# LED_s_1Teclado.net
KiCad netlist of a schematic drawn in Altium Designer
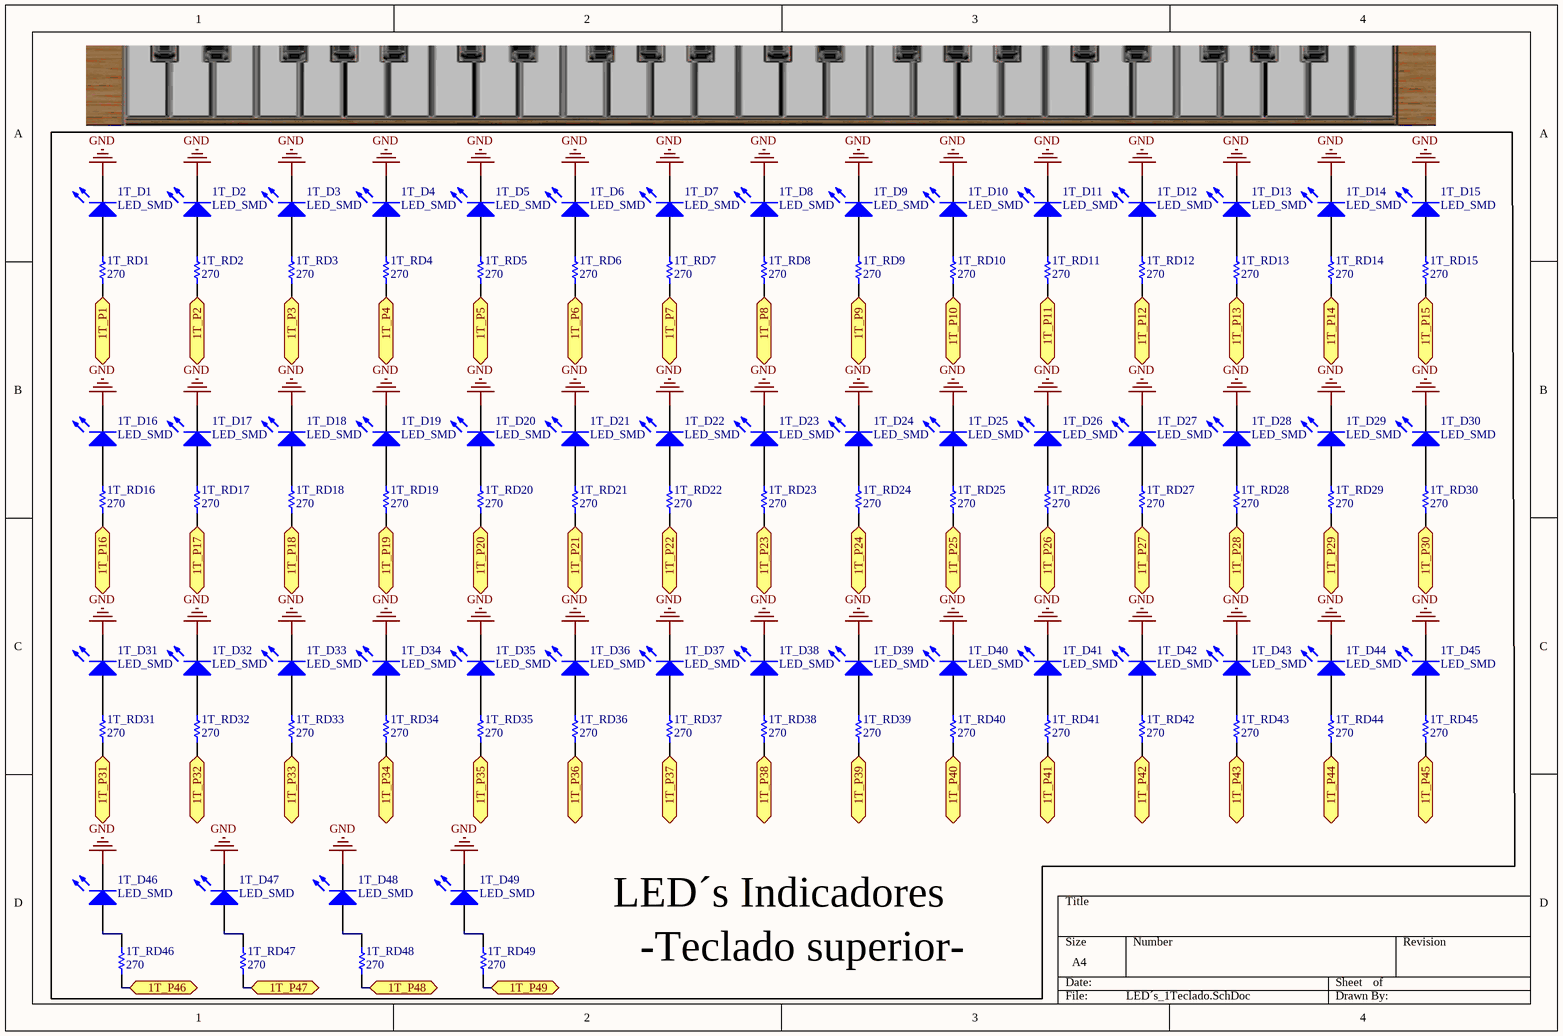
[diagram p0: LED´s_1Teclado.SchDoc]

(export (version "E")
  (design (tool "Eeschema 10.0.6"))
  (components
    (comp (ref "1T_D1")
      (value "LED_SMD")
      (footprint "0805")
      (description "LED SMD")
      (fields (field (name "PUBLISHER") "Altium Limited"))
      (libsource (lib "Libreria_Organo") (part "LED_SMD"))
    )
    (comp (ref "1T_D2")
      (value "LED_SMD")
      (footprint "0805")
      (description "LED SMD")
      (fields (field (name "PUBLISHER") "Altium Limited"))
      (libsource (lib "Libreria_Organo") (part "LED_SMD"))
    )
    (comp (ref "1T_D3")
      (value "LED_SMD")
      (footprint "0805")
      (description "LED SMD")
      (fields (field (name "PUBLISHER") "Altium Limited"))
      (libsource (lib "Libreria_Organo") (part "LED_SMD"))
    )
    (comp (ref "1T_D4")
      (value "LED_SMD")
      (footprint "0805")
      (description "LED SMD")
      (fields (field (name "PUBLISHER") "Altium Limited"))
      (libsource (lib "Libreria_Organo") (part "LED_SMD"))
    )
    (comp (ref "1T_D5")
      (value "LED_SMD")
      (footprint "0805")
      (description "LED SMD")
      (fields (field (name "PUBLISHER") "Altium Limited"))
      (libsource (lib "Libreria_Organo") (part "LED_SMD"))
    )
    (comp (ref "1T_D6")
      (value "LED_SMD")
      (footprint "0805")
      (description "LED SMD")
      (fields (field (name "PUBLISHER") "Altium Limited"))
      (libsource (lib "Libreria_Organo") (part "LED_SMD"))
    )
    (comp (ref "1T_D7")
      (value "LED_SMD")
      (footprint "0805")
      (description "LED SMD")
      (fields (field (name "PUBLISHER") "Altium Limited"))
      (libsource (lib "Libreria_Organo") (part "LED_SMD"))
    )
    (comp (ref "1T_D8")
      (value "LED_SMD")
      (footprint "0805")
      (description "LED SMD")
      (fields (field (name "PUBLISHER") "Altium Limited"))
      (libsource (lib "Libreria_Organo") (part "LED_SMD"))
    )
    (comp (ref "1T_D9")
      (value "LED_SMD")
      (footprint "0805")
      (description "LED SMD")
      (fields (field (name "PUBLISHER") "Altium Limited"))
      (libsource (lib "Libreria_Organo") (part "LED_SMD"))
    )
    (comp (ref "1T_D10")
      (value "LED_SMD")
      (footprint "0805")
      (description "LED SMD")
      (fields (field (name "PUBLISHER") "Altium Limited"))
      (libsource (lib "Libreria_Organo") (part "LED_SMD"))
    )
    (comp (ref "1T_D11")
      (value "LED_SMD")
      (footprint "0805")
      (description "LED SMD")
      (fields (field (name "PUBLISHER") "Altium Limited"))
      (libsource (lib "Libreria_Organo") (part "LED_SMD"))
    )
    (comp (ref "1T_D12")
      (value "LED_SMD")
      (footprint "0805")
      (description "LED SMD")
      (fields (field (name "PUBLISHER") "Altium Limited"))
      (libsource (lib "Libreria_Organo") (part "LED_SMD"))
    )
    (comp (ref "1T_D13")
      (value "LED_SMD")
      (footprint "0805")
      (description "LED SMD")
      (fields (field (name "PUBLISHER") "Altium Limited"))
      (libsource (lib "Libreria_Organo") (part "LED_SMD"))
    )
    (comp (ref "1T_D14")
      (value "LED_SMD")
      (footprint "0805")
      (description "LED SMD")
      (fields (field (name "PUBLISHER") "Altium Limited"))
      (libsource (lib "Libreria_Organo") (part "LED_SMD"))
    )
    (comp (ref "1T_D15")
      (value "LED_SMD")
      (footprint "0805")
      (description "LED SMD")
      (fields (field (name "PUBLISHER") "Altium Limited"))
      (libsource (lib "Libreria_Organo") (part "LED_SMD"))
    )
    (comp (ref "1T_D16")
      (value "LED_SMD")
      (footprint "0805")
      (description "LED SMD")
      (fields (field (name "PUBLISHER") "Altium Limited"))
      (libsource (lib "Libreria_Organo") (part "LED_SMD"))
    )
    (comp (ref "1T_D17")
      (value "LED_SMD")
      (footprint "0805")
      (description "LED SMD")
      (fields (field (name "PUBLISHER") "Altium Limited"))
      (libsource (lib "Libreria_Organo") (part "LED_SMD"))
    )
    (comp (ref "1T_D18")
      (value "LED_SMD")
      (footprint "0805")
      (description "LED SMD")
      (fields (field (name "PUBLISHER") "Altium Limited"))
      (libsource (lib "Libreria_Organo") (part "LED_SMD"))
    )
    (comp (ref "1T_D19")
      (value "LED_SMD")
      (footprint "0805")
      (description "LED SMD")
      (fields (field (name "PUBLISHER") "Altium Limited"))
      (libsource (lib "Libreria_Organo") (part "LED_SMD"))
    )
    (comp (ref "1T_D20")
      (value "LED_SMD")
      (footprint "0805")
      (description "LED SMD")
      (fields (field (name "PUBLISHER") "Altium Limited"))
      (libsource (lib "Libreria_Organo") (part "LED_SMD"))
    )
    (comp (ref "1T_D21")
      (value "LED_SMD")
      (footprint "0805")
      (description "LED SMD")
      (fields (field (name "PUBLISHER") "Altium Limited"))
      (libsource (lib "Libreria_Organo") (part "LED_SMD"))
    )
    (comp (ref "1T_D22")
      (value "LED_SMD")
      (footprint "0805")
      (description "LED SMD")
      (fields (field (name "PUBLISHER") "Altium Limited"))
      (libsource (lib "Libreria_Organo") (part "LED_SMD"))
    )
    (comp (ref "1T_D23")
      (value "LED_SMD")
      (footprint "0805")
      (description "LED SMD")
      (fields (field (name "PUBLISHER") "Altium Limited"))
      (libsource (lib "Libreria_Organo") (part "LED_SMD"))
    )
    (comp (ref "1T_D24")
      (value "LED_SMD")
      (footprint "0805")
      (description "LED SMD")
      (fields (field (name "PUBLISHER") "Altium Limited"))
      (libsource (lib "Libreria_Organo") (part "LED_SMD"))
    )
    (comp (ref "1T_D25")
      (value "LED_SMD")
      (footprint "0805")
      (description "LED SMD")
      (fields (field (name "PUBLISHER") "Altium Limited"))
      (libsource (lib "Libreria_Organo") (part "LED_SMD"))
    )
    (comp (ref "1T_D26")
      (value "LED_SMD")
      (footprint "0805")
      (description "LED SMD")
      (fields (field (name "PUBLISHER") "Altium Limited"))
      (libsource (lib "Libreria_Organo") (part "LED_SMD"))
    )
    (comp (ref "1T_D27")
      (value "LED_SMD")
      (footprint "0805")
      (description "LED SMD")
      (fields (field (name "PUBLISHER") "Altium Limited"))
      (libsource (lib "Libreria_Organo") (part "LED_SMD"))
    )
    (comp (ref "1T_D28")
      (value "LED_SMD")
      (footprint "0805")
      (description "LED SMD")
      (fields (field (name "PUBLISHER") "Altium Limited"))
      (libsource (lib "Libreria_Organo") (part "LED_SMD"))
    )
    (comp (ref "1T_D29")
      (value "LED_SMD")
      (footprint "0805")
      (description "LED SMD")
      (fields (field (name "PUBLISHER") "Altium Limited"))
      (libsource (lib "Libreria_Organo") (part "LED_SMD"))
    )
    (comp (ref "1T_D30")
      (value "LED_SMD")
      (footprint "0805")
      (description "LED SMD")
      (fields (field (name "PUBLISHER") "Altium Limited"))
      (libsource (lib "Libreria_Organo") (part "LED_SMD"))
    )
    (comp (ref "1T_D31")
      (value "LED_SMD")
      (footprint "0805")
      (description "LED SMD")
      (fields (field (name "PUBLISHER") "Altium Limited"))
      (libsource (lib "Libreria_Organo") (part "LED_SMD"))
    )
    (comp (ref "1T_D32")
      (value "LED_SMD")
      (footprint "0805")
      (description "LED SMD")
      (fields (field (name "PUBLISHER") "Altium Limited"))
      (libsource (lib "Libreria_Organo") (part "LED_SMD"))
    )
    (comp (ref "1T_D33")
      (value "LED_SMD")
      (footprint "0805")
      (description "LED SMD")
      (fields (field (name "PUBLISHER") "Altium Limited"))
      (libsource (lib "Libreria_Organo") (part "LED_SMD"))
    )
    (comp (ref "1T_D34")
      (value "LED_SMD")
      (footprint "0805")
      (description "LED SMD")
      (fields (field (name "PUBLISHER") "Altium Limited"))
      (libsource (lib "Libreria_Organo") (part "LED_SMD"))
    )
    (comp (ref "1T_D35")
      (value "LED_SMD")
      (footprint "0805")
      (description "LED SMD")
      (fields (field (name "PUBLISHER") "Altium Limited"))
      (libsource (lib "Libreria_Organo") (part "LED_SMD"))
    )
    (comp (ref "1T_D36")
      (value "LED_SMD")
      (footprint "0805")
      (description "LED SMD")
      (fields (field (name "PUBLISHER") "Altium Limited"))
      (libsource (lib "Libreria_Organo") (part "LED_SMD"))
    )
    (comp (ref "1T_D37")
      (value "LED_SMD")
      (footprint "0805")
      (description "LED SMD")
      (fields (field (name "PUBLISHER") "Altium Limited"))
      (libsource (lib "Libreria_Organo") (part "LED_SMD"))
    )
    (comp (ref "1T_D38")
      (value "LED_SMD")
      (footprint "0805")
      (description "LED SMD")
      (fields (field (name "PUBLISHER") "Altium Limited"))
      (libsource (lib "Libreria_Organo") (part "LED_SMD"))
    )
    (comp (ref "1T_D39")
      (value "LED_SMD")
      (footprint "0805")
      (description "LED SMD")
      (fields (field (name "PUBLISHER") "Altium Limited"))
      (libsource (lib "Libreria_Organo") (part "LED_SMD"))
    )
    (comp (ref "1T_D40")
      (value "LED_SMD")
      (footprint "0805")
      (description "LED SMD")
      (fields (field (name "PUBLISHER") "Altium Limited"))
      (libsource (lib "Libreria_Organo") (part "LED_SMD"))
    )
    (comp (ref "1T_D41")
      (value "LED_SMD")
      (footprint "0805")
      (description "LED SMD")
      (fields (field (name "PUBLISHER") "Altium Limited"))
      (libsource (lib "Libreria_Organo") (part "LED_SMD"))
    )
    (comp (ref "1T_D42")
      (value "LED_SMD")
      (footprint "0805")
      (description "LED SMD")
      (fields (field (name "PUBLISHER") "Altium Limited"))
      (libsource (lib "Libreria_Organo") (part "LED_SMD"))
    )
    (comp (ref "1T_D43")
      (value "LED_SMD")
      (footprint "0805")
      (description "LED SMD")
      (fields (field (name "PUBLISHER") "Altium Limited"))
      (libsource (lib "Libreria_Organo") (part "LED_SMD"))
    )
    (comp (ref "1T_D44")
      (value "LED_SMD")
      (footprint "0805")
      (description "LED SMD")
      (fields (field (name "PUBLISHER") "Altium Limited"))
      (libsource (lib "Libreria_Organo") (part "LED_SMD"))
    )
    (comp (ref "1T_D45")
      (value "LED_SMD")
      (footprint "0805")
      (description "LED SMD")
      (fields (field (name "PUBLISHER") "Altium Limited"))
      (libsource (lib "Libreria_Organo") (part "LED_SMD"))
    )
    (comp (ref "1T_D46")
      (value "LED_SMD")
      (footprint "0805")
      (description "LED SMD")
      (fields (field (name "PUBLISHER") "Altium Limited"))
      (libsource (lib "Libreria_Organo") (part "LED_SMD"))
    )
    (comp (ref "1T_D47")
      (value "LED_SMD")
      (footprint "0805")
      (description "LED SMD")
      (fields (field (name "PUBLISHER") "Altium Limited"))
      (libsource (lib "Libreria_Organo") (part "LED_SMD"))
    )
    (comp (ref "1T_D48")
      (value "LED_SMD")
      (footprint "0805")
      (description "LED SMD")
      (fields (field (name "PUBLISHER") "Altium Limited"))
      (libsource (lib "Libreria_Organo") (part "LED_SMD"))
    )
    (comp (ref "1T_D49")
      (value "LED_SMD")
      (footprint "0805")
      (description "LED SMD")
      (fields (field (name "PUBLISHER") "Altium Limited"))
      (libsource (lib "Libreria_Organo") (part "LED_SMD"))
    )
    (comp (ref "1T_RD1")
      (value "270")
      (footprint "0805 Chip Res")
      (description "Res Chip 0805")
      (fields (field (name "PUBLISHER") "Altium Limited"))
      (libsource (lib "Libreria_Organo") (part "Resistencia"))
    )
    (comp (ref "1T_RD2")
      (value "270")
      (footprint "0805 Chip Res")
      (description "Res Chip 0805")
      (fields (field (name "PUBLISHER") "Altium Limited"))
      (libsource (lib "Libreria_Organo") (part "Resistencia"))
    )
    (comp (ref "1T_RD3")
      (value "270")
      (footprint "0805 Chip Res")
      (description "Res Chip 0805")
      (fields (field (name "PUBLISHER") "Altium Limited"))
      (libsource (lib "Libreria_Organo") (part "Resistencia"))
    )
    (comp (ref "1T_RD4")
      (value "270")
      (footprint "0805 Chip Res")
      (description "Res Chip 0805")
      (fields (field (name "PUBLISHER") "Altium Limited"))
      (libsource (lib "Libreria_Organo") (part "Resistencia"))
    )
    (comp (ref "1T_RD5")
      (value "270")
      (footprint "0805 Chip Res")
      (description "Res Chip 0805")
      (fields (field (name "PUBLISHER") "Altium Limited"))
      (libsource (lib "Libreria_Organo") (part "Resistencia"))
    )
    (comp (ref "1T_RD6")
      (value "270")
      (footprint "0805 Chip Res")
      (description "Res Chip 0805")
      (fields (field (name "PUBLISHER") "Altium Limited"))
      (libsource (lib "Libreria_Organo") (part "Resistencia"))
    )
    (comp (ref "1T_RD7")
      (value "270")
      (footprint "0805 Chip Res")
      (description "Res Chip 0805")
      (fields (field (name "PUBLISHER") "Altium Limited"))
      (libsource (lib "Libreria_Organo") (part "Resistencia"))
    )
    (comp (ref "1T_RD8")
      (value "270")
      (footprint "0805 Chip Res")
      (description "Res Chip 0805")
      (fields (field (name "PUBLISHER") "Altium Limited"))
      (libsource (lib "Libreria_Organo") (part "Resistencia"))
    )
    (comp (ref "1T_RD9")
      (value "270")
      (footprint "0805 Chip Res")
      (description "Res Chip 0805")
      (fields (field (name "PUBLISHER") "Altium Limited"))
      (libsource (lib "Libreria_Organo") (part "Resistencia"))
    )
    (comp (ref "1T_RD10")
      (value "270")
      (footprint "0805 Chip Res")
      (description "Res Chip 0805")
      (fields (field (name "PUBLISHER") "Altium Limited"))
      (libsource (lib "Libreria_Organo") (part "Resistencia"))
    )
    (comp (ref "1T_RD11")
      (value "270")
      (footprint "0805 Chip Res")
      (description "Res Chip 0805")
      (fields (field (name "PUBLISHER") "Altium Limited"))
      (libsource (lib "Libreria_Organo") (part "Resistencia"))
    )
    (comp (ref "1T_RD12")
      (value "270")
      (footprint "0805 Chip Res")
      (description "Res Chip 0805")
      (fields (field (name "PUBLISHER") "Altium Limited"))
      (libsource (lib "Libreria_Organo") (part "Resistencia"))
    )
    (comp (ref "1T_RD13")
      (value "270")
      (footprint "0805 Chip Res")
      (description "Res Chip 0805")
      (fields (field (name "PUBLISHER") "Altium Limited"))
      (libsource (lib "Libreria_Organo") (part "Resistencia"))
    )
    (comp (ref "1T_RD14")
      (value "270")
      (footprint "0805 Chip Res")
      (description "Res Chip 0805")
      (fields (field (name "PUBLISHER") "Altium Limited"))
      (libsource (lib "Libreria_Organo") (part "Resistencia"))
    )
    (comp (ref "1T_RD15")
      (value "270")
      (footprint "0805 Chip Res")
      (description "Res Chip 0805")
      (fields (field (name "PUBLISHER") "Altium Limited"))
      (libsource (lib "Libreria_Organo") (part "Resistencia"))
    )
    (comp (ref "1T_RD16")
      (value "270")
      (footprint "0805 Chip Res")
      (description "Res Chip 0805")
      (fields (field (name "PUBLISHER") "Altium Limited"))
      (libsource (lib "Libreria_Organo") (part "Resistencia"))
    )
    (comp (ref "1T_RD17")
      (value "270")
      (footprint "0805 Chip Res")
      (description "Res Chip 0805")
      (fields (field (name "PUBLISHER") "Altium Limited"))
      (libsource (lib "Libreria_Organo") (part "Resistencia"))
    )
    (comp (ref "1T_RD18")
      (value "270")
      (footprint "0805 Chip Res")
      (description "Res Chip 0805")
      (fields (field (name "PUBLISHER") "Altium Limited"))
      (libsource (lib "Libreria_Organo") (part "Resistencia"))
    )
    (comp (ref "1T_RD19")
      (value "270")
      (footprint "0805 Chip Res")
      (description "Res Chip 0805")
      (fields (field (name "PUBLISHER") "Altium Limited"))
      (libsource (lib "Libreria_Organo") (part "Resistencia"))
    )
    (comp (ref "1T_RD20")
      (value "270")
      (footprint "0805 Chip Res")
      (description "Res Chip 0805")
      (fields (field (name "PUBLISHER") "Altium Limited"))
      (libsource (lib "Libreria_Organo") (part "Resistencia"))
    )
    (comp (ref "1T_RD21")
      (value "270")
      (footprint "0805 Chip Res")
      (description "Res Chip 0805")
      (fields (field (name "PUBLISHER") "Altium Limited"))
      (libsource (lib "Libreria_Organo") (part "Resistencia"))
    )
    (comp (ref "1T_RD22")
      (value "270")
      (footprint "0805 Chip Res")
      (description "Res Chip 0805")
      (fields (field (name "PUBLISHER") "Altium Limited"))
      (libsource (lib "Libreria_Organo") (part "Resistencia"))
    )
    (comp (ref "1T_RD23")
      (value "270")
      (footprint "0805 Chip Res")
      (description "Res Chip 0805")
      (fields (field (name "PUBLISHER") "Altium Limited"))
      (libsource (lib "Libreria_Organo") (part "Resistencia"))
    )
    (comp (ref "1T_RD24")
      (value "270")
      (footprint "0805 Chip Res")
      (description "Res Chip 0805")
      (fields (field (name "PUBLISHER") "Altium Limited"))
      (libsource (lib "Libreria_Organo") (part "Resistencia"))
    )
    (comp (ref "1T_RD25")
      (value "270")
      (footprint "0805 Chip Res")
      (description "Res Chip 0805")
      (fields (field (name "PUBLISHER") "Altium Limited"))
      (libsource (lib "Libreria_Organo") (part "Resistencia"))
    )
    (comp (ref "1T_RD26")
      (value "270")
      (footprint "0805 Chip Res")
      (description "Res Chip 0805")
      (fields (field (name "PUBLISHER") "Altium Limited"))
      (libsource (lib "Libreria_Organo") (part "Resistencia"))
    )
    (comp (ref "1T_RD27")
      (value "270")
      (footprint "0805 Chip Res")
      (description "Res Chip 0805")
      (fields (field (name "PUBLISHER") "Altium Limited"))
      (libsource (lib "Libreria_Organo") (part "Resistencia"))
    )
    (comp (ref "1T_RD28")
      (value "270")
      (footprint "0805 Chip Res")
      (description "Res Chip 0805")
      (fields (field (name "PUBLISHER") "Altium Limited"))
      (libsource (lib "Libreria_Organo") (part "Resistencia"))
    )
    (comp (ref "1T_RD29")
      (value "270")
      (footprint "0805 Chip Res")
      (description "Res Chip 0805")
      (fields (field (name "PUBLISHER") "Altium Limited"))
      (libsource (lib "Libreria_Organo") (part "Resistencia"))
    )
    (comp (ref "1T_RD30")
      (value "270")
      (footprint "0805 Chip Res")
      (description "Res Chip 0805")
      (fields (field (name "PUBLISHER") "Altium Limited"))
      (libsource (lib "Libreria_Organo") (part "Resistencia"))
    )
    (comp (ref "1T_RD31")
      (value "270")
      (footprint "0805 Chip Res")
      (description "Res Chip 0805")
      (fields (field (name "PUBLISHER") "Altium Limited"))
      (libsource (lib "Libreria_Organo") (part "Resistencia"))
    )
    (comp (ref "1T_RD32")
      (value "270")
      (footprint "0805 Chip Res")
      (description "Res Chip 0805")
      (fields (field (name "PUBLISHER") "Altium Limited"))
      (libsource (lib "Libreria_Organo") (part "Resistencia"))
    )
    (comp (ref "1T_RD33")
      (value "270")
      (footprint "0805 Chip Res")
      (description "Res Chip 0805")
      (fields (field (name "PUBLISHER") "Altium Limited"))
      (libsource (lib "Libreria_Organo") (part "Resistencia"))
    )
    (comp (ref "1T_RD34")
      (value "270")
      (footprint "0805 Chip Res")
      (description "Res Chip 0805")
      (fields (field (name "PUBLISHER") "Altium Limited"))
      (libsource (lib "Libreria_Organo") (part "Resistencia"))
    )
    (comp (ref "1T_RD35")
      (value "270")
      (footprint "0805 Chip Res")
      (description "Res Chip 0805")
      (fields (field (name "PUBLISHER") "Altium Limited"))
      (libsource (lib "Libreria_Organo") (part "Resistencia"))
    )
    (comp (ref "1T_RD36")
      (value "270")
      (footprint "0805 Chip Res")
      (description "Res Chip 0805")
      (fields (field (name "PUBLISHER") "Altium Limited"))
      (libsource (lib "Libreria_Organo") (part "Resistencia"))
    )
    (comp (ref "1T_RD37")
      (value "270")
      (footprint "0805 Chip Res")
      (description "Res Chip 0805")
      (fields (field (name "PUBLISHER") "Altium Limited"))
      (libsource (lib "Libreria_Organo") (part "Resistencia"))
    )
    (comp (ref "1T_RD38")
      (value "270")
      (footprint "0805 Chip Res")
      (description "Res Chip 0805")
      (fields (field (name "PUBLISHER") "Altium Limited"))
      (libsource (lib "Libreria_Organo") (part "Resistencia"))
    )
    (comp (ref "1T_RD39")
      (value "270")
      (footprint "0805 Chip Res")
      (description "Res Chip 0805")
      (fields (field (name "PUBLISHER") "Altium Limited"))
      (libsource (lib "Libreria_Organo") (part "Resistencia"))
    )
    (comp (ref "1T_RD40")
      (value "270")
      (footprint "0805 Chip Res")
      (description "Res Chip 0805")
      (fields (field (name "PUBLISHER") "Altium Limited"))
      (libsource (lib "Libreria_Organo") (part "Resistencia"))
    )
    (comp (ref "1T_RD41")
      (value "270")
      (footprint "0805 Chip Res")
      (description "Res Chip 0805")
      (fields (field (name "PUBLISHER") "Altium Limited"))
      (libsource (lib "Libreria_Organo") (part "Resistencia"))
    )
    (comp (ref "1T_RD42")
      (value "270")
      (footprint "0805 Chip Res")
      (description "Res Chip 0805")
      (fields (field (name "PUBLISHER") "Altium Limited"))
      (libsource (lib "Libreria_Organo") (part "Resistencia"))
    )
    (comp (ref "1T_RD43")
      (value "270")
      (footprint "0805 Chip Res")
      (description "Res Chip 0805")
      (fields (field (name "PUBLISHER") "Altium Limited"))
      (libsource (lib "Libreria_Organo") (part "Resistencia"))
    )
    (comp (ref "1T_RD44")
      (value "270")
      (footprint "0805 Chip Res")
      (description "Res Chip 0805")
      (fields (field (name "PUBLISHER") "Altium Limited"))
      (libsource (lib "Libreria_Organo") (part "Resistencia"))
    )
    (comp (ref "1T_RD45")
      (value "270")
      (footprint "0805 Chip Res")
      (description "Res Chip 0805")
      (fields (field (name "PUBLISHER") "Altium Limited"))
      (libsource (lib "Libreria_Organo") (part "Resistencia"))
    )
    (comp (ref "1T_RD46")
      (value "270")
      (footprint "0805 Chip Res")
      (description "Res Chip 0805")
      (fields (field (name "PUBLISHER") "Altium Limited"))
      (libsource (lib "Libreria_Organo") (part "Resistencia"))
    )
    (comp (ref "1T_RD47")
      (value "270")
      (footprint "0805 Chip Res")
      (description "Res Chip 0805")
      (fields (field (name "PUBLISHER") "Altium Limited"))
      (libsource (lib "Libreria_Organo") (part "Resistencia"))
    )
    (comp (ref "1T_RD48")
      (value "270")
      (footprint "0805 Chip Res")
      (description "Res Chip 0805")
      (fields (field (name "PUBLISHER") "Altium Limited"))
      (libsource (lib "Libreria_Organo") (part "Resistencia"))
    )
    (comp (ref "1T_RD49")
      (value "270")
      (footprint "0805 Chip Res")
      (description "Res Chip 0805")
      (fields (field (name "PUBLISHER") "Altium Limited"))
      (libsource (lib "Libreria_Organo") (part "Resistencia"))
    )
  )
  (nets
    (net (code "1") (name "/1T_P1") (class "Default")
      (node (ref "1T_RD1") (pin "1") (pinfunction "1_1") (pintype "passive"))
    )
    (net (code "2") (name "/1T_P2") (class "Default")
      (node (ref "1T_RD2") (pin "1") (pinfunction "1_1") (pintype "passive"))
    )
    (net (code "3") (name "/1T_P3") (class "Default")
      (node (ref "1T_RD3") (pin "1") (pinfunction "1_1") (pintype "passive"))
    )
    (net (code "4") (name "/1T_P4") (class "Default")
      (node (ref "1T_RD4") (pin "1") (pinfunction "1_1") (pintype "passive"))
    )
    (net (code "5") (name "/1T_P5") (class "Default")
      (node (ref "1T_RD5") (pin "1") (pinfunction "1_1") (pintype "passive"))
    )
    (net (code "6") (name "/1T_P6") (class "Default")
      (node (ref "1T_RD6") (pin "1") (pinfunction "1_1") (pintype "passive"))
    )
    (net (code "7") (name "/1T_P7") (class "Default")
      (node (ref "1T_RD7") (pin "1") (pinfunction "1_1") (pintype "passive"))
    )
    (net (code "8") (name "/1T_P8") (class "Default")
      (node (ref "1T_RD8") (pin "1") (pinfunction "1_1") (pintype "passive"))
    )
    (net (code "9") (name "/1T_P9") (class "Default")
      (node (ref "1T_RD9") (pin "1") (pinfunction "1_1") (pintype "passive"))
    )
    (net (code "10") (name "/1T_P10") (class "Default")
      (node (ref "1T_RD10") (pin "1") (pinfunction "1_1") (pintype "passive"))
    )
    (net (code "11") (name "/1T_P11") (class "Default")
      (node (ref "1T_RD11") (pin "1") (pinfunction "1_1") (pintype "passive"))
    )
    (net (code "12") (name "/1T_P12") (class "Default")
      (node (ref "1T_RD12") (pin "1") (pinfunction "1_1") (pintype "passive"))
    )
    (net (code "13") (name "/1T_P13") (class "Default")
      (node (ref "1T_RD13") (pin "1") (pinfunction "1_1") (pintype "passive"))
    )
    (net (code "14") (name "/1T_P14") (class "Default")
      (node (ref "1T_RD14") (pin "1") (pinfunction "1_1") (pintype "passive"))
    )
    (net (code "15") (name "/1T_P15") (class "Default")
      (node (ref "1T_RD15") (pin "1") (pinfunction "1_1") (pintype "passive"))
    )
    (net (code "16") (name "/1T_P16") (class "Default")
      (node (ref "1T_RD16") (pin "1") (pinfunction "1_1") (pintype "passive"))
    )
    (net (code "17") (name "/1T_P17") (class "Default")
      (node (ref "1T_RD17") (pin "1") (pinfunction "1_1") (pintype "passive"))
    )
    (net (code "18") (name "/1T_P18") (class "Default")
      (node (ref "1T_RD18") (pin "1") (pinfunction "1_1") (pintype "passive"))
    )
    (net (code "19") (name "/1T_P19") (class "Default")
      (node (ref "1T_RD19") (pin "1") (pinfunction "1_1") (pintype "passive"))
    )
    (net (code "20") (name "/1T_P20") (class "Default")
      (node (ref "1T_RD20") (pin "1") (pinfunction "1_1") (pintype "passive"))
    )
    (net (code "21") (name "/1T_P21") (class "Default")
      (node (ref "1T_RD21") (pin "1") (pinfunction "1_1") (pintype "passive"))
    )
    (net (code "22") (name "/1T_P22") (class "Default")
      (node (ref "1T_RD22") (pin "1") (pinfunction "1_1") (pintype "passive"))
    )
    (net (code "23") (name "/1T_P23") (class "Default")
      (node (ref "1T_RD23") (pin "1") (pinfunction "1_1") (pintype "passive"))
    )
    (net (code "24") (name "/1T_P24") (class "Default")
      (node (ref "1T_RD24") (pin "1") (pinfunction "1_1") (pintype "passive"))
    )
    (net (code "25") (name "/1T_P25") (class "Default")
      (node (ref "1T_RD25") (pin "1") (pinfunction "1_1") (pintype "passive"))
    )
    (net (code "26") (name "/1T_P26") (class "Default")
      (node (ref "1T_RD26") (pin "1") (pinfunction "1_1") (pintype "passive"))
    )
    (net (code "27") (name "/1T_P27") (class "Default")
      (node (ref "1T_RD27") (pin "1") (pinfunction "1_1") (pintype "passive"))
    )
    (net (code "28") (name "/1T_P28") (class "Default")
      (node (ref "1T_RD28") (pin "1") (pinfunction "1_1") (pintype "passive"))
    )
    (net (code "29") (name "/1T_P29") (class "Default")
      (node (ref "1T_RD29") (pin "1") (pinfunction "1_1") (pintype "passive"))
    )
    (net (code "30") (name "/1T_P30") (class "Default")
      (node (ref "1T_RD30") (pin "1") (pinfunction "1_1") (pintype "passive"))
    )
    (net (code "31") (name "/1T_P31") (class "Default")
      (node (ref "1T_RD31") (pin "1") (pinfunction "1_1") (pintype "passive"))
    )
    (net (code "32") (name "/1T_P32") (class "Default")
      (node (ref "1T_RD32") (pin "1") (pinfunction "1_1") (pintype "passive"))
    )
    (net (code "33") (name "/1T_P33") (class "Default")
      (node (ref "1T_RD33") (pin "1") (pinfunction "1_1") (pintype "passive"))
    )
    (net (code "34") (name "/1T_P34") (class "Default")
      (node (ref "1T_RD34") (pin "1") (pinfunction "1_1") (pintype "passive"))
    )
    (net (code "35") (name "/1T_P35") (class "Default")
      (node (ref "1T_RD35") (pin "1") (pinfunction "1_1") (pintype "passive"))
    )
    (net (code "36") (name "/1T_P36") (class "Default")
      (node (ref "1T_RD36") (pin "1") (pinfunction "1_1") (pintype "passive"))
    )
    (net (code "37") (name "/1T_P37") (class "Default")
      (node (ref "1T_RD37") (pin "1") (pinfunction "1_1") (pintype "passive"))
    )
    (net (code "38") (name "/1T_P38") (class "Default")
      (node (ref "1T_RD38") (pin "1") (pinfunction "1_1") (pintype "passive"))
    )
    (net (code "39") (name "/1T_P39") (class "Default")
      (node (ref "1T_RD39") (pin "1") (pinfunction "1_1") (pintype "passive"))
    )
    (net (code "40") (name "/1T_P40") (class "Default")
      (node (ref "1T_RD40") (pin "1") (pinfunction "1_1") (pintype "passive"))
    )
    (net (code "41") (name "/1T_P41") (class "Default")
      (node (ref "1T_RD41") (pin "1") (pinfunction "1_1") (pintype "passive"))
    )
    (net (code "42") (name "/1T_P42") (class "Default")
      (node (ref "1T_RD42") (pin "1") (pinfunction "1_1") (pintype "passive"))
    )
    (net (code "43") (name "/1T_P43") (class "Default")
      (node (ref "1T_RD43") (pin "1") (pinfunction "1_1") (pintype "passive"))
    )
    (net (code "44") (name "/1T_P44") (class "Default")
      (node (ref "1T_RD44") (pin "1") (pinfunction "1_1") (pintype "passive"))
    )
    (net (code "45") (name "/1T_P45") (class "Default")
      (node (ref "1T_RD45") (pin "1") (pinfunction "1_1") (pintype "passive"))
    )
    (net (code "46") (name "/1T_P46") (class "Default")
      (node (ref "1T_RD46") (pin "1") (pinfunction "1_1") (pintype "passive"))
    )
    (net (code "47") (name "/1T_P47") (class "Default")
      (node (ref "1T_RD47") (pin "1") (pinfunction "1_1") (pintype "passive"))
    )
    (net (code "48") (name "/1T_P48") (class "Default")
      (node (ref "1T_RD48") (pin "1") (pinfunction "1_1") (pintype "passive"))
    )
    (net (code "49") (name "/1T_P49") (class "Default")
      (node (ref "1T_RD49") (pin "1") (pinfunction "1_1") (pintype "passive"))
    )
    (net (code "50") (name "GND") (class "Default")
      (node (ref "1T_D1") (pin "2") (pinfunction "K_2") (pintype "passive"))
      (node (ref "1T_D10") (pin "2") (pinfunction "K_2") (pintype "passive"))
      (node (ref "1T_D11") (pin "2") (pinfunction "K_2") (pintype "passive"))
      (node (ref "1T_D12") (pin "2") (pinfunction "K_2") (pintype "passive"))
      (node (ref "1T_D13") (pin "2") (pinfunction "K_2") (pintype "passive"))
      (node (ref "1T_D14") (pin "2") (pinfunction "K_2") (pintype "passive"))
      (node (ref "1T_D15") (pin "2") (pinfunction "K_2") (pintype "passive"))
      (node (ref "1T_D16") (pin "2") (pinfunction "K_2") (pintype "passive"))
      (node (ref "1T_D17") (pin "2") (pinfunction "K_2") (pintype "passive"))
      (node (ref "1T_D18") (pin "2") (pinfunction "K_2") (pintype "passive"))
      (node (ref "1T_D19") (pin "2") (pinfunction "K_2") (pintype "passive"))
      (node (ref "1T_D2") (pin "2") (pinfunction "K_2") (pintype "passive"))
      (node (ref "1T_D20") (pin "2") (pinfunction "K_2") (pintype "passive"))
      (node (ref "1T_D21") (pin "2") (pinfunction "K_2") (pintype "passive"))
      (node (ref "1T_D22") (pin "2") (pinfunction "K_2") (pintype "passive"))
      (node (ref "1T_D23") (pin "2") (pinfunction "K_2") (pintype "passive"))
      (node (ref "1T_D24") (pin "2") (pinfunction "K_2") (pintype "passive"))
      (node (ref "1T_D25") (pin "2") (pinfunction "K_2") (pintype "passive"))
      (node (ref "1T_D26") (pin "2") (pinfunction "K_2") (pintype "passive"))
      (node (ref "1T_D27") (pin "2") (pinfunction "K_2") (pintype "passive"))
      (node (ref "1T_D28") (pin "2") (pinfunction "K_2") (pintype "passive"))
      (node (ref "1T_D29") (pin "2") (pinfunction "K_2") (pintype "passive"))
      (node (ref "1T_D3") (pin "2") (pinfunction "K_2") (pintype "passive"))
      (node (ref "1T_D30") (pin "2") (pinfunction "K_2") (pintype "passive"))
      (node (ref "1T_D31") (pin "2") (pinfunction "K_2") (pintype "passive"))
      (node (ref "1T_D32") (pin "2") (pinfunction "K_2") (pintype "passive"))
      (node (ref "1T_D33") (pin "2") (pinfunction "K_2") (pintype "passive"))
      (node (ref "1T_D34") (pin "2") (pinfunction "K_2") (pintype "passive"))
      (node (ref "1T_D35") (pin "2") (pinfunction "K_2") (pintype "passive"))
      (node (ref "1T_D36") (pin "2") (pinfunction "K_2") (pintype "passive"))
      (node (ref "1T_D37") (pin "2") (pinfunction "K_2") (pintype "passive"))
      (node (ref "1T_D38") (pin "2") (pinfunction "K_2") (pintype "passive"))
      (node (ref "1T_D39") (pin "2") (pinfunction "K_2") (pintype "passive"))
      (node (ref "1T_D4") (pin "2") (pinfunction "K_2") (pintype "passive"))
      (node (ref "1T_D40") (pin "2") (pinfunction "K_2") (pintype "passive"))
      (node (ref "1T_D41") (pin "2") (pinfunction "K_2") (pintype "passive"))
      (node (ref "1T_D42") (pin "2") (pinfunction "K_2") (pintype "passive"))
      (node (ref "1T_D43") (pin "2") (pinfunction "K_2") (pintype "passive"))
      (node (ref "1T_D44") (pin "2") (pinfunction "K_2") (pintype "passive"))
      (node (ref "1T_D45") (pin "2") (pinfunction "K_2") (pintype "passive"))
      (node (ref "1T_D46") (pin "2") (pinfunction "K_2") (pintype "passive"))
      (node (ref "1T_D47") (pin "2") (pinfunction "K_2") (pintype "passive"))
      (node (ref "1T_D48") (pin "2") (pinfunction "K_2") (pintype "passive"))
      (node (ref "1T_D49") (pin "2") (pinfunction "K_2") (pintype "passive"))
      (node (ref "1T_D5") (pin "2") (pinfunction "K_2") (pintype "passive"))
      (node (ref "1T_D6") (pin "2") (pinfunction "K_2") (pintype "passive"))
      (node (ref "1T_D7") (pin "2") (pinfunction "K_2") (pintype "passive"))
      (node (ref "1T_D8") (pin "2") (pinfunction "K_2") (pintype "passive"))
      (node (ref "1T_D9") (pin "2") (pinfunction "K_2") (pintype "passive"))
    )
    (net (code "51") (name "Net-(1T_D1-A)") (class "Default")
      (node (ref "1T_D1") (pin "1") (pinfunction "A_1") (pintype "passive"))
      (node (ref "1T_RD1") (pin "2") (pinfunction "2_2") (pintype "passive"))
    )
    (net (code "52") (name "Net-(1T_D2-A)") (class "Default")
      (node (ref "1T_D2") (pin "1") (pinfunction "A_1") (pintype "passive"))
      (node (ref "1T_RD2") (pin "2") (pinfunction "2_2") (pintype "passive"))
    )
    (net (code "53") (name "Net-(1T_D3-A)") (class "Default")
      (node (ref "1T_D3") (pin "1") (pinfunction "A_1") (pintype "passive"))
      (node (ref "1T_RD3") (pin "2") (pinfunction "2_2") (pintype "passive"))
    )
    (net (code "54") (name "Net-(1T_D4-A)") (class "Default")
      (node (ref "1T_D4") (pin "1") (pinfunction "A_1") (pintype "passive"))
      (node (ref "1T_RD4") (pin "2") (pinfunction "2_2") (pintype "passive"))
    )
    (net (code "55") (name "Net-(1T_D5-A)") (class "Default")
      (node (ref "1T_D5") (pin "1") (pinfunction "A_1") (pintype "passive"))
      (node (ref "1T_RD5") (pin "2") (pinfunction "2_2") (pintype "passive"))
    )
    (net (code "56") (name "Net-(1T_D6-A)") (class "Default")
      (node (ref "1T_D6") (pin "1") (pinfunction "A_1") (pintype "passive"))
      (node (ref "1T_RD6") (pin "2") (pinfunction "2_2") (pintype "passive"))
    )
    (net (code "57") (name "Net-(1T_D7-A)") (class "Default")
      (node (ref "1T_D7") (pin "1") (pinfunction "A_1") (pintype "passive"))
      (node (ref "1T_RD7") (pin "2") (pinfunction "2_2") (pintype "passive"))
    )
    (net (code "58") (name "Net-(1T_D8-A)") (class "Default")
      (node (ref "1T_D8") (pin "1") (pinfunction "A_1") (pintype "passive"))
      (node (ref "1T_RD8") (pin "2") (pinfunction "2_2") (pintype "passive"))
    )
    (net (code "59") (name "Net-(1T_D9-A)") (class "Default")
      (node (ref "1T_D9") (pin "1") (pinfunction "A_1") (pintype "passive"))
      (node (ref "1T_RD9") (pin "2") (pinfunction "2_2") (pintype "passive"))
    )
    (net (code "60") (name "Net-(1T_D10-A)") (class "Default")
      (node (ref "1T_D10") (pin "1") (pinfunction "A_1") (pintype "passive"))
      (node (ref "1T_RD10") (pin "2") (pinfunction "2_2") (pintype "passive"))
    )
    (net (code "61") (name "Net-(1T_D11-A)") (class "Default")
      (node (ref "1T_D11") (pin "1") (pinfunction "A_1") (pintype "passive"))
      (node (ref "1T_RD11") (pin "2") (pinfunction "2_2") (pintype "passive"))
    )
    (net (code "62") (name "Net-(1T_D12-A)") (class "Default")
      (node (ref "1T_D12") (pin "1") (pinfunction "A_1") (pintype "passive"))
      (node (ref "1T_RD12") (pin "2") (pinfunction "2_2") (pintype "passive"))
    )
    (net (code "63") (name "Net-(1T_D13-A)") (class "Default")
      (node (ref "1T_D13") (pin "1") (pinfunction "A_1") (pintype "passive"))
      (node (ref "1T_RD13") (pin "2") (pinfunction "2_2") (pintype "passive"))
    )
    (net (code "64") (name "Net-(1T_D14-A)") (class "Default")
      (node (ref "1T_D14") (pin "1") (pinfunction "A_1") (pintype "passive"))
      (node (ref "1T_RD14") (pin "2") (pinfunction "2_2") (pintype "passive"))
    )
    (net (code "65") (name "Net-(1T_D15-A)") (class "Default")
      (node (ref "1T_D15") (pin "1") (pinfunction "A_1") (pintype "passive"))
      (node (ref "1T_RD15") (pin "2") (pinfunction "2_2") (pintype "passive"))
    )
    (net (code "66") (name "Net-(1T_D16-A)") (class "Default")
      (node (ref "1T_D16") (pin "1") (pinfunction "A_1") (pintype "passive"))
      (node (ref "1T_RD16") (pin "2") (pinfunction "2_2") (pintype "passive"))
    )
    (net (code "67") (name "Net-(1T_D17-A)") (class "Default")
      (node (ref "1T_D17") (pin "1") (pinfunction "A_1") (pintype "passive"))
      (node (ref "1T_RD17") (pin "2") (pinfunction "2_2") (pintype "passive"))
    )
    (net (code "68") (name "Net-(1T_D18-A)") (class "Default")
      (node (ref "1T_D18") (pin "1") (pinfunction "A_1") (pintype "passive"))
      (node (ref "1T_RD18") (pin "2") (pinfunction "2_2") (pintype "passive"))
    )
    (net (code "69") (name "Net-(1T_D19-A)") (class "Default")
      (node (ref "1T_D19") (pin "1") (pinfunction "A_1") (pintype "passive"))
      (node (ref "1T_RD19") (pin "2") (pinfunction "2_2") (pintype "passive"))
    )
    (net (code "70") (name "Net-(1T_D20-A)") (class "Default")
      (node (ref "1T_D20") (pin "1") (pinfunction "A_1") (pintype "passive"))
      (node (ref "1T_RD20") (pin "2") (pinfunction "2_2") (pintype "passive"))
    )
    (net (code "71") (name "Net-(1T_D21-A)") (class "Default")
      (node (ref "1T_D21") (pin "1") (pinfunction "A_1") (pintype "passive"))
      (node (ref "1T_RD21") (pin "2") (pinfunction "2_2") (pintype "passive"))
    )
    (net (code "72") (name "Net-(1T_D22-A)") (class "Default")
      (node (ref "1T_D22") (pin "1") (pinfunction "A_1") (pintype "passive"))
      (node (ref "1T_RD22") (pin "2") (pinfunction "2_2") (pintype "passive"))
    )
    (net (code "73") (name "Net-(1T_D23-A)") (class "Default")
      (node (ref "1T_D23") (pin "1") (pinfunction "A_1") (pintype "passive"))
      (node (ref "1T_RD23") (pin "2") (pinfunction "2_2") (pintype "passive"))
    )
    (net (code "74") (name "Net-(1T_D24-A)") (class "Default")
      (node (ref "1T_D24") (pin "1") (pinfunction "A_1") (pintype "passive"))
      (node (ref "1T_RD24") (pin "2") (pinfunction "2_2") (pintype "passive"))
    )
    (net (code "75") (name "Net-(1T_D25-A)") (class "Default")
      (node (ref "1T_D25") (pin "1") (pinfunction "A_1") (pintype "passive"))
      (node (ref "1T_RD25") (pin "2") (pinfunction "2_2") (pintype "passive"))
    )
    (net (code "76") (name "Net-(1T_D26-A)") (class "Default")
      (node (ref "1T_D26") (pin "1") (pinfunction "A_1") (pintype "passive"))
      (node (ref "1T_RD26") (pin "2") (pinfunction "2_2") (pintype "passive"))
    )
    (net (code "77") (name "Net-(1T_D27-A)") (class "Default")
      (node (ref "1T_D27") (pin "1") (pinfunction "A_1") (pintype "passive"))
      (node (ref "1T_RD27") (pin "2") (pinfunction "2_2") (pintype "passive"))
    )
    (net (code "78") (name "Net-(1T_D28-A)") (class "Default")
      (node (ref "1T_D28") (pin "1") (pinfunction "A_1") (pintype "passive"))
      (node (ref "1T_RD28") (pin "2") (pinfunction "2_2") (pintype "passive"))
    )
    (net (code "79") (name "Net-(1T_D29-A)") (class "Default")
      (node (ref "1T_D29") (pin "1") (pinfunction "A_1") (pintype "passive"))
      (node (ref "1T_RD29") (pin "2") (pinfunction "2_2") (pintype "passive"))
    )
    (net (code "80") (name "Net-(1T_D30-A)") (class "Default")
      (node (ref "1T_D30") (pin "1") (pinfunction "A_1") (pintype "passive"))
      (node (ref "1T_RD30") (pin "2") (pinfunction "2_2") (pintype "passive"))
    )
    (net (code "81") (name "Net-(1T_D31-A)") (class "Default")
      (node (ref "1T_D31") (pin "1") (pinfunction "A_1") (pintype "passive"))
      (node (ref "1T_RD31") (pin "2") (pinfunction "2_2") (pintype "passive"))
    )
    (net (code "82") (name "Net-(1T_D32-A)") (class "Default")
      (node (ref "1T_D32") (pin "1") (pinfunction "A_1") (pintype "passive"))
      (node (ref "1T_RD32") (pin "2") (pinfunction "2_2") (pintype "passive"))
    )
    (net (code "83") (name "Net-(1T_D33-A)") (class "Default")
      (node (ref "1T_D33") (pin "1") (pinfunction "A_1") (pintype "passive"))
      (node (ref "1T_RD33") (pin "2") (pinfunction "2_2") (pintype "passive"))
    )
    (net (code "84") (name "Net-(1T_D34-A)") (class "Default")
      (node (ref "1T_D34") (pin "1") (pinfunction "A_1") (pintype "passive"))
      (node (ref "1T_RD34") (pin "2") (pinfunction "2_2") (pintype "passive"))
    )
    (net (code "85") (name "Net-(1T_D35-A)") (class "Default")
      (node (ref "1T_D35") (pin "1") (pinfunction "A_1") (pintype "passive"))
      (node (ref "1T_RD35") (pin "2") (pinfunction "2_2") (pintype "passive"))
    )
    (net (code "86") (name "Net-(1T_D36-A)") (class "Default")
      (node (ref "1T_D36") (pin "1") (pinfunction "A_1") (pintype "passive"))
      (node (ref "1T_RD36") (pin "2") (pinfunction "2_2") (pintype "passive"))
    )
    (net (code "87") (name "Net-(1T_D37-A)") (class "Default")
      (node (ref "1T_D37") (pin "1") (pinfunction "A_1") (pintype "passive"))
      (node (ref "1T_RD37") (pin "2") (pinfunction "2_2") (pintype "passive"))
    )
    (net (code "88") (name "Net-(1T_D38-A)") (class "Default")
      (node (ref "1T_D38") (pin "1") (pinfunction "A_1") (pintype "passive"))
      (node (ref "1T_RD38") (pin "2") (pinfunction "2_2") (pintype "passive"))
    )
    (net (code "89") (name "Net-(1T_D39-A)") (class "Default")
      (node (ref "1T_D39") (pin "1") (pinfunction "A_1") (pintype "passive"))
      (node (ref "1T_RD39") (pin "2") (pinfunction "2_2") (pintype "passive"))
    )
    (net (code "90") (name "Net-(1T_D40-A)") (class "Default")
      (node (ref "1T_D40") (pin "1") (pinfunction "A_1") (pintype "passive"))
      (node (ref "1T_RD40") (pin "2") (pinfunction "2_2") (pintype "passive"))
    )
    (net (code "91") (name "Net-(1T_D41-A)") (class "Default")
      (node (ref "1T_D41") (pin "1") (pinfunction "A_1") (pintype "passive"))
      (node (ref "1T_RD41") (pin "2") (pinfunction "2_2") (pintype "passive"))
    )
    (net (code "92") (name "Net-(1T_D42-A)") (class "Default")
      (node (ref "1T_D42") (pin "1") (pinfunction "A_1") (pintype "passive"))
      (node (ref "1T_RD42") (pin "2") (pinfunction "2_2") (pintype "passive"))
    )
    (net (code "93") (name "Net-(1T_D43-A)") (class "Default")
      (node (ref "1T_D43") (pin "1") (pinfunction "A_1") (pintype "passive"))
      (node (ref "1T_RD43") (pin "2") (pinfunction "2_2") (pintype "passive"))
    )
    (net (code "94") (name "Net-(1T_D44-A)") (class "Default")
      (node (ref "1T_D44") (pin "1") (pinfunction "A_1") (pintype "passive"))
      (node (ref "1T_RD44") (pin "2") (pinfunction "2_2") (pintype "passive"))
    )
    (net (code "95") (name "Net-(1T_D45-A)") (class "Default")
      (node (ref "1T_D45") (pin "1") (pinfunction "A_1") (pintype "passive"))
      (node (ref "1T_RD45") (pin "2") (pinfunction "2_2") (pintype "passive"))
    )
    (net (code "96") (name "Net-(1T_D46-A)") (class "Default")
      (node (ref "1T_D46") (pin "1") (pinfunction "A_1") (pintype "passive"))
      (node (ref "1T_RD46") (pin "2") (pinfunction "2_2") (pintype "passive"))
    )
    (net (code "97") (name "Net-(1T_D47-A)") (class "Default")
      (node (ref "1T_D47") (pin "1") (pinfunction "A_1") (pintype "passive"))
      (node (ref "1T_RD47") (pin "2") (pinfunction "2_2") (pintype "passive"))
    )
    (net (code "98") (name "Net-(1T_D48-A)") (class "Default")
      (node (ref "1T_D48") (pin "1") (pinfunction "A_1") (pintype "passive"))
      (node (ref "1T_RD48") (pin "2") (pinfunction "2_2") (pintype "passive"))
    )
    (net (code "99") (name "Net-(1T_D49-A)") (class "Default")
      (node (ref "1T_D49") (pin "1") (pinfunction "A_1") (pintype "passive"))
      (node (ref "1T_RD49") (pin "2") (pinfunction "2_2") (pintype "passive"))
    )
  )
)
